# ExtensionConnector.net
KiCad netlist of a schematic drawn in Altium Designer
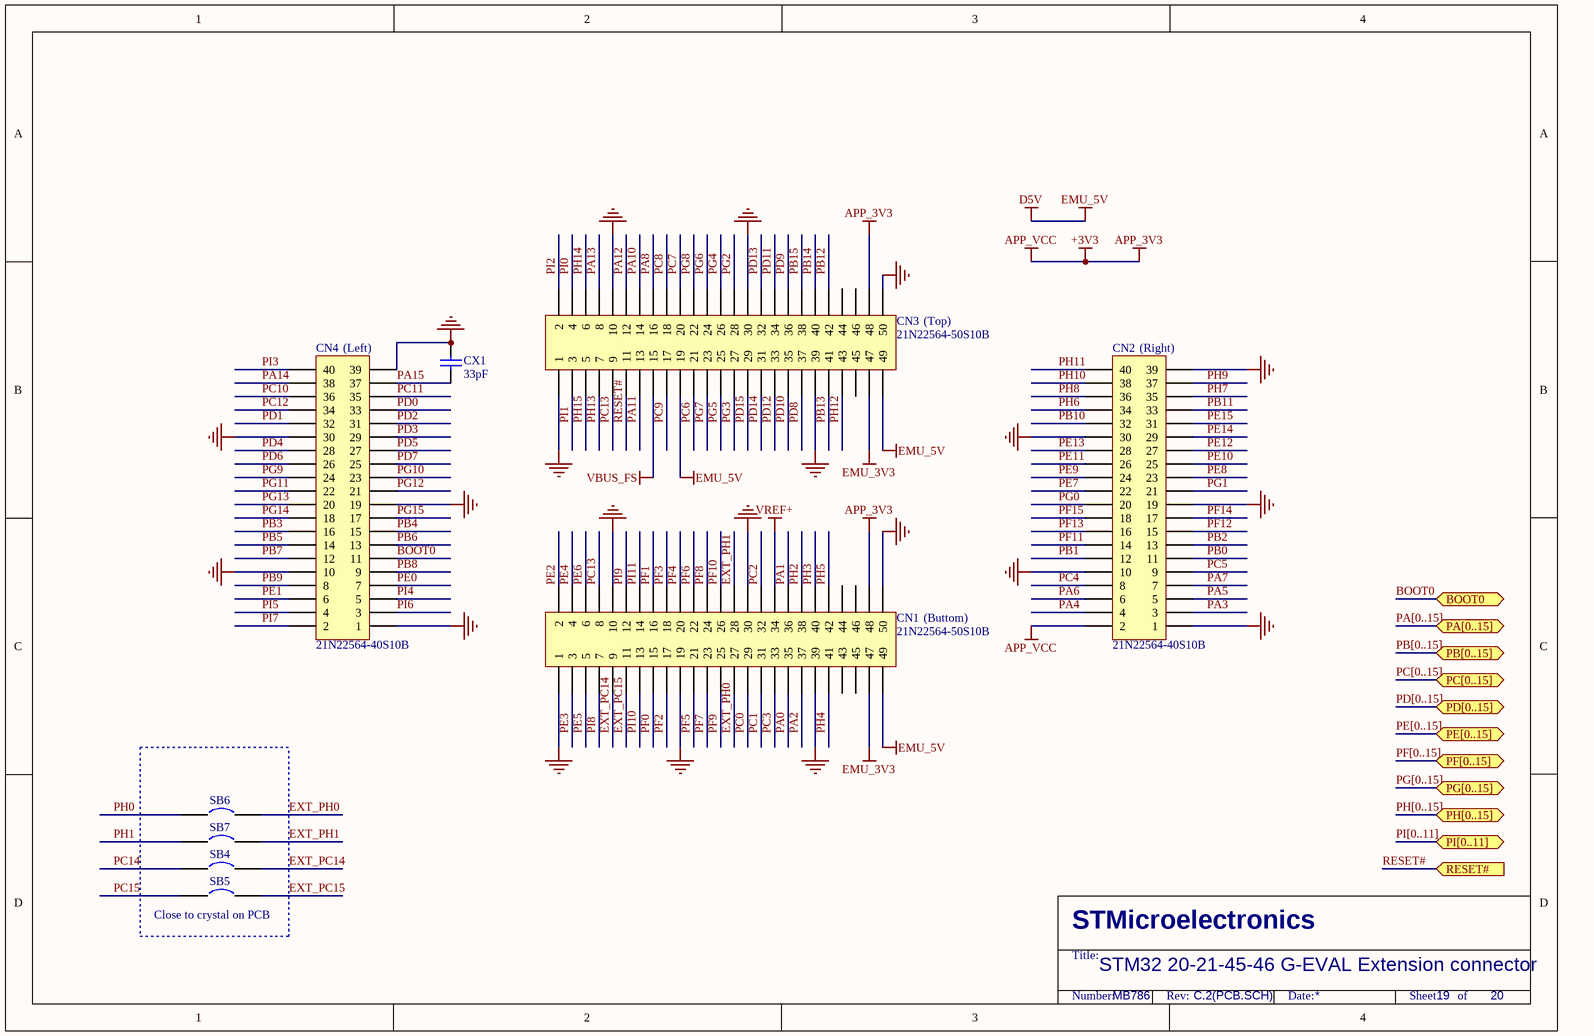
[diagram p0: ExtensionConnector.SchDoc]

(export (version "E")
  (design (tool "Eeschema 10.0.6"))
  (components
    (comp (ref "CN1")
      (value "21N22564-50S10B")
      (footprint "2*25p")
      (description "Header, 25-Pin, Dual row")
      (fields (field (name "PUBLISHER") "Altium Limited"))
      (libsource (lib "Miscellaneous Connectors") (part "Header 25X2"))
    )
    (comp (ref "CN2")
      (value "21N22564-40S10B")
      (footprint "2*20p")
      (description "Header, 20-Pin, Dual row")
      (fields (field (name "PUBLISHER") "Altium Limited"))
      (libsource (lib "Miscellaneous Connectors") (part "Header 20X2"))
    )
    (comp (ref "CN3")
      (value "21N22564-50S10B")
      (footprint "2*25p")
      (description "Header, 25-Pin, Dual row")
      (fields (field (name "PUBLISHER") "Altium Limited"))
      (libsource (lib "Miscellaneous Connectors") (part "Header 25X2"))
    )
    (comp (ref "CN4")
      (value "21N22564-40S10B")
      (footprint "2*20p")
      (description "Header, 20-Pin, Dual row")
      (fields (field (name "PUBLISHER") "Altium Limited"))
      (libsource (lib "Miscellaneous Connectors") (part "Header 20X2"))
    )
    (comp (ref "CX1")
      (value "33pF")
      (footprint "0402C")
      (description "Capacitor")
      (fields (field (name "PUBLISHER") "Altium Limited"))
      (libsource (lib "Miscellaneous Devices") (part "Cap"))
    )
    (comp (ref "SB4")
      (value "~")
      (footprint "JP2_SMD")
      (description "Circuit Breaker")
      (fields (field (name "PUBLISHER") "Altium Limited"))
      (libsource (lib "Miscellaneous Devices") (part "Circuit Breaker"))
    )
    (comp (ref "SB5")
      (value "~")
      (footprint "JP2_SMD")
      (description "Circuit Breaker")
      (fields (field (name "PUBLISHER") "Altium Limited"))
      (libsource (lib "Miscellaneous Devices") (part "Circuit Breaker"))
    )
    (comp (ref "SB6")
      (value "~")
      (footprint "JP2_SMD")
      (description "Circuit Breaker")
      (fields (field (name "PUBLISHER") "Altium Limited"))
      (libsource (lib "Miscellaneous Devices") (part "Circuit Breaker"))
    )
    (comp (ref "SB7")
      (value "~")
      (footprint "JP2_SMD")
      (description "Circuit Breaker")
      (fields (field (name "PUBLISHER") "Altium Limited"))
      (libsource (lib "Miscellaneous Devices") (part "Circuit Breaker"))
    )
  )
  (nets
    (net (code "2") (name "+3V3") (class "Default")
      (node (ref "CN1") (pin "48") (pinfunction "48_48") (pintype "passive"))
      (node (ref "CN2") (pin "2") (pinfunction "2_2") (pintype "passive"))
      (node (ref "CN3") (pin "48") (pinfunction "48_48") (pintype "passive"))
    )
    (net (code "3") (name "/BOOT0") (class "Default")
      (node (ref "CN4") (pin "11") (pinfunction "11_11") (pintype "passive"))
    )
    (net (code "4") (name "/EXT_PC14") (class "Default")
      (node (ref "CN1") (pin "9") (pinfunction "9_9") (pintype "passive"))
      (node (ref "SB4") (pin "2") (pinfunction "2_2") (pintype "passive"))
    )
    (net (code "5") (name "/EXT_PC15") (class "Default")
      (node (ref "CN1") (pin "11") (pinfunction "11_11") (pintype "passive"))
      (node (ref "SB5") (pin "2") (pinfunction "2_2") (pintype "passive"))
    )
    (net (code "6") (name "/EXT_PH0") (class "Default")
      (node (ref "CN1") (pin "27") (pinfunction "27_27") (pintype "passive"))
      (node (ref "SB6") (pin "2") (pinfunction "2_2") (pintype "passive"))
    )
    (net (code "7") (name "/EXT_PH1") (class "Default")
      (node (ref "CN1") (pin "28") (pinfunction "28_28") (pintype "passive"))
      (node (ref "SB7") (pin "2") (pinfunction "2_2") (pintype "passive"))
    )
    (net (code "8") (name "/PA0") (class "Default")
      (node (ref "CN1") (pin "35") (pinfunction "35_35") (pintype "passive"))
    )
    (net (code "9") (name "/PA1") (class "Default")
      (node (ref "CN1") (pin "36") (pinfunction "36_36") (pintype "passive"))
    )
    (net (code "10") (name "/PA2") (class "Default")
      (node (ref "CN1") (pin "37") (pinfunction "37_37") (pintype "passive"))
    )
    (net (code "11") (name "/PA3") (class "Default")
      (node (ref "CN2") (pin "3") (pinfunction "3_3") (pintype "passive"))
    )
    (net (code "12") (name "/PA4") (class "Default")
      (node (ref "CN2") (pin "4") (pinfunction "4_4") (pintype "passive"))
    )
    (net (code "13") (name "/PA5") (class "Default")
      (node (ref "CN2") (pin "5") (pinfunction "5_5") (pintype "passive"))
    )
    (net (code "14") (name "/PA6") (class "Default")
      (node (ref "CN2") (pin "6") (pinfunction "6_6") (pintype "passive"))
    )
    (net (code "15") (name "/PA7") (class "Default")
      (node (ref "CN2") (pin "7") (pinfunction "7_7") (pintype "passive"))
    )
    (net (code "16") (name "/PA8") (class "Default")
      (node (ref "CN3") (pin "16") (pinfunction "16_16") (pintype "passive"))
    )
    (net (code "17") (name "/PA10") (class "Default")
      (node (ref "CN3") (pin "14") (pinfunction "14_14") (pintype "passive"))
    )
    (net (code "18") (name "/PA11") (class "Default")
      (node (ref "CN3") (pin "13") (pinfunction "13_13") (pintype "passive"))
    )
    (net (code "19") (name "/PA12") (class "Default")
      (node (ref "CN3") (pin "12") (pinfunction "12_12") (pintype "passive"))
    )
    (net (code "20") (name "/PA13") (class "Default")
      (node (ref "CN3") (pin "8") (pinfunction "8_8") (pintype "passive"))
    )
    (net (code "21") (name "/PA14") (class "Default")
      (node (ref "CN4") (pin "38") (pinfunction "38_38") (pintype "passive"))
    )
    (net (code "22") (name "/PA15") (class "Default")
      (node (ref "CN4") (pin "37") (pinfunction "37_37") (pintype "passive"))
      (node (ref "CX1") (pin "1") (pinfunction "1_1") (pintype "passive"))
    )
    (net (code "24") (name "/PB0") (class "Default")
      (node (ref "CN2") (pin "11") (pinfunction "11_11") (pintype "passive"))
    )
    (net (code "25") (name "/PB1") (class "Default")
      (node (ref "CN2") (pin "12") (pinfunction "12_12") (pintype "passive"))
    )
    (net (code "26") (name "/PB2") (class "Default")
      (node (ref "CN2") (pin "13") (pinfunction "13_13") (pintype "passive"))
    )
    (net (code "27") (name "/PB3") (class "Default")
      (node (ref "CN4") (pin "16") (pinfunction "16_16") (pintype "passive"))
    )
    (net (code "28") (name "/PB4") (class "Default")
      (node (ref "CN4") (pin "15") (pinfunction "15_15") (pintype "passive"))
    )
    (net (code "29") (name "/PB5") (class "Default")
      (node (ref "CN4") (pin "14") (pinfunction "14_14") (pintype "passive"))
    )
    (net (code "30") (name "/PB6") (class "Default")
      (node (ref "CN4") (pin "13") (pinfunction "13_13") (pintype "passive"))
    )
    (net (code "31") (name "/PB7") (class "Default")
      (node (ref "CN4") (pin "12") (pinfunction "12_12") (pintype "passive"))
    )
    (net (code "32") (name "/PB8") (class "Default")
      (node (ref "CN4") (pin "9") (pinfunction "9_9") (pintype "passive"))
    )
    (net (code "33") (name "/PB9") (class "Default")
      (node (ref "CN4") (pin "8") (pinfunction "8_8") (pintype "passive"))
    )
    (net (code "34") (name "/PB10") (class "Default")
      (node (ref "CN2") (pin "32") (pinfunction "32_32") (pintype "passive"))
    )
    (net (code "35") (name "/PB11") (class "Default")
      (node (ref "CN2") (pin "33") (pinfunction "33_33") (pintype "passive"))
    )
    (net (code "36") (name "/PB12") (class "Default")
      (node (ref "CN3") (pin "42") (pinfunction "42_42") (pintype "passive"))
    )
    (net (code "37") (name "/PB13") (class "Default")
      (node (ref "CN3") (pin "41") (pinfunction "41_41") (pintype "passive"))
    )
    (net (code "38") (name "/PB14") (class "Default")
      (node (ref "CN3") (pin "40") (pinfunction "40_40") (pintype "passive"))
    )
    (net (code "39") (name "/PB15") (class "Default")
      (node (ref "CN3") (pin "38") (pinfunction "38_38") (pintype "passive"))
    )
    (net (code "41") (name "/PC0") (class "Default")
      (node (ref "CN1") (pin "29") (pinfunction "29_29") (pintype "passive"))
    )
    (net (code "42") (name "/PC1") (class "Default")
      (node (ref "CN1") (pin "31") (pinfunction "31_31") (pintype "passive"))
    )
    (net (code "43") (name "/PC2") (class "Default")
      (node (ref "CN1") (pin "32") (pinfunction "32_32") (pintype "passive"))
    )
    (net (code "44") (name "/PC3") (class "Default")
      (node (ref "CN1") (pin "33") (pinfunction "33_33") (pintype "passive"))
    )
    (net (code "45") (name "/PC4") (class "Default")
      (node (ref "CN2") (pin "8") (pinfunction "8_8") (pintype "passive"))
    )
    (net (code "46") (name "/PC5") (class "Default")
      (node (ref "CN2") (pin "9") (pinfunction "9_9") (pintype "passive"))
    )
    (net (code "47") (name "/PC6") (class "Default")
      (node (ref "CN3") (pin "21") (pinfunction "21_21") (pintype "passive"))
    )
    (net (code "48") (name "/PC7") (class "Default")
      (node (ref "CN3") (pin "20") (pinfunction "20_20") (pintype "passive"))
    )
    (net (code "49") (name "/PC8") (class "Default")
      (node (ref "CN3") (pin "18") (pinfunction "18_18") (pintype "passive"))
    )
    (net (code "50") (name "/PC9") (class "Default")
      (node (ref "CN3") (pin "17") (pinfunction "17_17") (pintype "passive"))
    )
    (net (code "51") (name "/PC10") (class "Default")
      (node (ref "CN4") (pin "36") (pinfunction "36_36") (pintype "passive"))
    )
    (net (code "52") (name "/PC11") (class "Default")
      (node (ref "CN4") (pin "35") (pinfunction "35_35") (pintype "passive"))
    )
    (net (code "53") (name "/PC12") (class "Default")
      (node (ref "CN4") (pin "34") (pinfunction "34_34") (pintype "passive"))
    )
    (net (code "54") (name "/PC13") (class "Default")
      (node (ref "CN1") (pin "8") (pinfunction "8_8") (pintype "passive"))
      (node (ref "CN3") (pin "9") (pinfunction "9_9") (pintype "passive"))
    )
    (net (code "55") (name "/PC14") (class "Default")
      (node (ref "SB4") (pin "1") (pinfunction "1_1") (pintype "passive"))
    )
    (net (code "56") (name "/PC15") (class "Default")
      (node (ref "SB5") (pin "1") (pinfunction "1_1") (pintype "passive"))
    )
    (net (code "58") (name "/PD0") (class "Default")
      (node (ref "CN4") (pin "33") (pinfunction "33_33") (pintype "passive"))
    )
    (net (code "59") (name "/PD1") (class "Default")
      (node (ref "CN4") (pin "32") (pinfunction "32_32") (pintype "passive"))
    )
    (net (code "60") (name "/PD2") (class "Default")
      (node (ref "CN4") (pin "31") (pinfunction "31_31") (pintype "passive"))
    )
    (net (code "61") (name "/PD3") (class "Default")
      (node (ref "CN4") (pin "29") (pinfunction "29_29") (pintype "passive"))
    )
    (net (code "62") (name "/PD4") (class "Default")
      (node (ref "CN4") (pin "28") (pinfunction "28_28") (pintype "passive"))
    )
    (net (code "63") (name "/PD5") (class "Default")
      (node (ref "CN4") (pin "27") (pinfunction "27_27") (pintype "passive"))
    )
    (net (code "64") (name "/PD6") (class "Default")
      (node (ref "CN4") (pin "26") (pinfunction "26_26") (pintype "passive"))
    )
    (net (code "65") (name "/PD7") (class "Default")
      (node (ref "CN4") (pin "25") (pinfunction "25_25") (pintype "passive"))
    )
    (net (code "66") (name "/PD8") (class "Default")
      (node (ref "CN3") (pin "37") (pinfunction "37_37") (pintype "passive"))
    )
    (net (code "67") (name "/PD9") (class "Default")
      (node (ref "CN3") (pin "36") (pinfunction "36_36") (pintype "passive"))
    )
    (net (code "68") (name "/PD10") (class "Default")
      (node (ref "CN3") (pin "35") (pinfunction "35_35") (pintype "passive"))
    )
    (net (code "69") (name "/PD11") (class "Default")
      (node (ref "CN3") (pin "34") (pinfunction "34_34") (pintype "passive"))
    )
    (net (code "70") (name "/PD12") (class "Default")
      (node (ref "CN3") (pin "33") (pinfunction "33_33") (pintype "passive"))
    )
    (net (code "71") (name "/PD13") (class "Default")
      (node (ref "CN3") (pin "32") (pinfunction "32_32") (pintype "passive"))
    )
    (net (code "72") (name "/PD14") (class "Default")
      (node (ref "CN3") (pin "31") (pinfunction "31_31") (pintype "passive"))
    )
    (net (code "73") (name "/PD15") (class "Default")
      (node (ref "CN3") (pin "29") (pinfunction "29_29") (pintype "passive"))
    )
    (net (code "75") (name "/PE0") (class "Default")
      (node (ref "CN4") (pin "7") (pinfunction "7_7") (pintype "passive"))
    )
    (net (code "76") (name "/PE1") (class "Default")
      (node (ref "CN4") (pin "6") (pinfunction "6_6") (pintype "passive"))
    )
    (net (code "77") (name "/PE2") (class "Default")
      (node (ref "CN1") (pin "2") (pinfunction "2_2") (pintype "passive"))
    )
    (net (code "78") (name "/PE3") (class "Default")
      (node (ref "CN1") (pin "3") (pinfunction "3_3") (pintype "passive"))
    )
    (net (code "79") (name "/PE4") (class "Default")
      (node (ref "CN1") (pin "4") (pinfunction "4_4") (pintype "passive"))
    )
    (net (code "80") (name "/PE5") (class "Default")
      (node (ref "CN1") (pin "5") (pinfunction "5_5") (pintype "passive"))
    )
    (net (code "81") (name "/PE6") (class "Default")
      (node (ref "CN1") (pin "6") (pinfunction "6_6") (pintype "passive"))
    )
    (net (code "82") (name "/PE7") (class "Default")
      (node (ref "CN2") (pin "22") (pinfunction "22_22") (pintype "passive"))
    )
    (net (code "83") (name "/PE8") (class "Default")
      (node (ref "CN2") (pin "23") (pinfunction "23_23") (pintype "passive"))
    )
    (net (code "84") (name "/PE9") (class "Default")
      (node (ref "CN2") (pin "24") (pinfunction "24_24") (pintype "passive"))
    )
    (net (code "85") (name "/PE10") (class "Default")
      (node (ref "CN2") (pin "25") (pinfunction "25_25") (pintype "passive"))
    )
    (net (code "86") (name "/PE11") (class "Default")
      (node (ref "CN2") (pin "26") (pinfunction "26_26") (pintype "passive"))
    )
    (net (code "87") (name "/PE12") (class "Default")
      (node (ref "CN2") (pin "27") (pinfunction "27_27") (pintype "passive"))
    )
    (net (code "88") (name "/PE13") (class "Default")
      (node (ref "CN2") (pin "28") (pinfunction "28_28") (pintype "passive"))
    )
    (net (code "89") (name "/PE14") (class "Default")
      (node (ref "CN2") (pin "29") (pinfunction "29_29") (pintype "passive"))
    )
    (net (code "90") (name "/PE15") (class "Default")
      (node (ref "CN2") (pin "31") (pinfunction "31_31") (pintype "passive"))
    )
    (net (code "92") (name "/PF0") (class "Default")
      (node (ref "CN1") (pin "15") (pinfunction "15_15") (pintype "passive"))
    )
    (net (code "93") (name "/PF1") (class "Default")
      (node (ref "CN1") (pin "16") (pinfunction "16_16") (pintype "passive"))
    )
    (net (code "94") (name "/PF2") (class "Default")
      (node (ref "CN1") (pin "17") (pinfunction "17_17") (pintype "passive"))
    )
    (net (code "95") (name "/PF3") (class "Default")
      (node (ref "CN1") (pin "18") (pinfunction "18_18") (pintype "passive"))
    )
    (net (code "96") (name "/PF4") (class "Default")
      (node (ref "CN1") (pin "20") (pinfunction "20_20") (pintype "passive"))
    )
    (net (code "97") (name "/PF5") (class "Default")
      (node (ref "CN1") (pin "21") (pinfunction "21_21") (pintype "passive"))
    )
    (net (code "98") (name "/PF6") (class "Default")
      (node (ref "CN1") (pin "22") (pinfunction "22_22") (pintype "passive"))
    )
    (net (code "99") (name "/PF7") (class "Default")
      (node (ref "CN1") (pin "23") (pinfunction "23_23") (pintype "passive"))
    )
    (net (code "100") (name "/PF8") (class "Default")
      (node (ref "CN1") (pin "24") (pinfunction "24_24") (pintype "passive"))
    )
    (net (code "101") (name "/PF9") (class "Default")
      (node (ref "CN1") (pin "25") (pinfunction "25_25") (pintype "passive"))
    )
    (net (code "102") (name "/PF10") (class "Default")
      (node (ref "CN1") (pin "26") (pinfunction "26_26") (pintype "passive"))
    )
    (net (code "103") (name "/PF11") (class "Default")
      (node (ref "CN2") (pin "14") (pinfunction "14_14") (pintype "passive"))
    )
    (net (code "104") (name "/PF12") (class "Default")
      (node (ref "CN2") (pin "15") (pinfunction "15_15") (pintype "passive"))
    )
    (net (code "105") (name "/PF13") (class "Default")
      (node (ref "CN2") (pin "16") (pinfunction "16_16") (pintype "passive"))
    )
    (net (code "106") (name "/PF14") (class "Default")
      (node (ref "CN2") (pin "17") (pinfunction "17_17") (pintype "passive"))
    )
    (net (code "107") (name "/PF15") (class "Default")
      (node (ref "CN2") (pin "18") (pinfunction "18_18") (pintype "passive"))
    )
    (net (code "109") (name "/PG0") (class "Default")
      (node (ref "CN2") (pin "20") (pinfunction "20_20") (pintype "passive"))
    )
    (net (code "110") (name "/PG1") (class "Default")
      (node (ref "CN2") (pin "21") (pinfunction "21_21") (pintype "passive"))
    )
    (net (code "111") (name "/PG2") (class "Default")
      (node (ref "CN3") (pin "28") (pinfunction "28_28") (pintype "passive"))
    )
    (net (code "112") (name "/PG3") (class "Default")
      (node (ref "CN3") (pin "27") (pinfunction "27_27") (pintype "passive"))
    )
    (net (code "113") (name "/PG4") (class "Default")
      (node (ref "CN3") (pin "26") (pinfunction "26_26") (pintype "passive"))
    )
    (net (code "114") (name "/PG5") (class "Default")
      (node (ref "CN3") (pin "25") (pinfunction "25_25") (pintype "passive"))
    )
    (net (code "115") (name "/PG6") (class "Default")
      (node (ref "CN3") (pin "24") (pinfunction "24_24") (pintype "passive"))
    )
    (net (code "116") (name "/PG7") (class "Default")
      (node (ref "CN3") (pin "23") (pinfunction "23_23") (pintype "passive"))
    )
    (net (code "117") (name "/PG8") (class "Default")
      (node (ref "CN3") (pin "22") (pinfunction "22_22") (pintype "passive"))
    )
    (net (code "118") (name "/PG9") (class "Default")
      (node (ref "CN4") (pin "24") (pinfunction "24_24") (pintype "passive"))
    )
    (net (code "119") (name "/PG10") (class "Default")
      (node (ref "CN4") (pin "23") (pinfunction "23_23") (pintype "passive"))
    )
    (net (code "120") (name "/PG11") (class "Default")
      (node (ref "CN4") (pin "22") (pinfunction "22_22") (pintype "passive"))
    )
    (net (code "121") (name "/PG12") (class "Default")
      (node (ref "CN4") (pin "21") (pinfunction "21_21") (pintype "passive"))
    )
    (net (code "122") (name "/PG13") (class "Default")
      (node (ref "CN4") (pin "20") (pinfunction "20_20") (pintype "passive"))
    )
    (net (code "123") (name "/PG14") (class "Default")
      (node (ref "CN4") (pin "18") (pinfunction "18_18") (pintype "passive"))
    )
    (net (code "124") (name "/PG15") (class "Default")
      (node (ref "CN4") (pin "17") (pinfunction "17_17") (pintype "passive"))
    )
    (net (code "126") (name "/PH0") (class "Default")
      (node (ref "SB6") (pin "1") (pinfunction "1_1") (pintype "passive"))
    )
    (net (code "127") (name "/PH1") (class "Default")
      (node (ref "SB7") (pin "1") (pinfunction "1_1") (pintype "passive"))
    )
    (net (code "128") (name "/PH2") (class "Default")
      (node (ref "CN1") (pin "38") (pinfunction "38_38") (pintype "passive"))
    )
    (net (code "129") (name "/PH3") (class "Default")
      (node (ref "CN1") (pin "40") (pinfunction "40_40") (pintype "passive"))
    )
    (net (code "130") (name "/PH4") (class "Default")
      (node (ref "CN1") (pin "41") (pinfunction "41_41") (pintype "passive"))
    )
    (net (code "131") (name "/PH5") (class "Default")
      (node (ref "CN1") (pin "42") (pinfunction "42_42") (pintype "passive"))
    )
    (net (code "132") (name "/PH6") (class "Default")
      (node (ref "CN2") (pin "34") (pinfunction "34_34") (pintype "passive"))
    )
    (net (code "133") (name "/PH7") (class "Default")
      (node (ref "CN2") (pin "35") (pinfunction "35_35") (pintype "passive"))
    )
    (net (code "134") (name "/PH8") (class "Default")
      (node (ref "CN2") (pin "36") (pinfunction "36_36") (pintype "passive"))
    )
    (net (code "135") (name "/PH9") (class "Default")
      (node (ref "CN2") (pin "37") (pinfunction "37_37") (pintype "passive"))
    )
    (net (code "136") (name "/PH10") (class "Default")
      (node (ref "CN2") (pin "38") (pinfunction "38_38") (pintype "passive"))
    )
    (net (code "137") (name "/PH11") (class "Default")
      (node (ref "CN2") (pin "40") (pinfunction "40_40") (pintype "passive"))
    )
    (net (code "138") (name "/PH12") (class "Default")
      (node (ref "CN3") (pin "43") (pinfunction "43_43") (pintype "passive"))
    )
    (net (code "139") (name "/PH13") (class "Default")
      (node (ref "CN3") (pin "7") (pinfunction "7_7") (pintype "passive"))
    )
    (net (code "140") (name "/PH14") (class "Default")
      (node (ref "CN3") (pin "6") (pinfunction "6_6") (pintype "passive"))
    )
    (net (code "141") (name "/PH15") (class "Default")
      (node (ref "CN3") (pin "5") (pinfunction "5_5") (pintype "passive"))
    )
    (net (code "143") (name "/PI0") (class "Default")
      (node (ref "CN3") (pin "4") (pinfunction "4_4") (pintype "passive"))
    )
    (net (code "144") (name "/PI1") (class "Default")
      (node (ref "CN3") (pin "3") (pinfunction "3_3") (pintype "passive"))
    )
    (net (code "145") (name "/PI2") (class "Default")
      (node (ref "CN3") (pin "2") (pinfunction "2_2") (pintype "passive"))
    )
    (net (code "146") (name "/PI3") (class "Default")
      (node (ref "CN4") (pin "40") (pinfunction "40_40") (pintype "passive"))
    )
    (net (code "147") (name "/PI4") (class "Default")
      (node (ref "CN4") (pin "5") (pinfunction "5_5") (pintype "passive"))
    )
    (net (code "148") (name "/PI5") (class "Default")
      (node (ref "CN4") (pin "4") (pinfunction "4_4") (pintype "passive"))
    )
    (net (code "149") (name "/PI6") (class "Default")
      (node (ref "CN4") (pin "3") (pinfunction "3_3") (pintype "passive"))
    )
    (net (code "150") (name "/PI7") (class "Default")
      (node (ref "CN4") (pin "2") (pinfunction "2_2") (pintype "passive"))
    )
    (net (code "151") (name "/PI8") (class "Default")
      (node (ref "CN1") (pin "7") (pinfunction "7_7") (pintype "passive"))
    )
    (net (code "152") (name "/PI9") (class "Default")
      (node (ref "CN1") (pin "12") (pinfunction "12_12") (pintype "passive"))
    )
    (net (code "153") (name "/PI10") (class "Default")
      (node (ref "CN1") (pin "13") (pinfunction "13_13") (pintype "passive"))
    )
    (net (code "154") (name "/PI11") (class "Default")
      (node (ref "CN1") (pin "14") (pinfunction "14_14") (pintype "passive"))
    )
    (net (code "156") (name "/RESET#") (class "Default")
      (node (ref "CN3") (pin "11") (pinfunction "11_11") (pintype "passive"))
    )
    (net (code "157") (name "D5V") (class "Default")
      (node (ref "CN1") (pin "49") (pinfunction "49_49") (pintype "passive"))
      (node (ref "CN3") (pin "19") (pinfunction "19_19") (pintype "passive"))
      (node (ref "CN3") (pin "49") (pinfunction "49_49") (pintype "passive"))
    )
    (net (code "158") (name "EMU_3V3") (class "Default")
      (node (ref "CN1") (pin "47") (pinfunction "47_47") (pintype "passive"))
      (node (ref "CN3") (pin "47") (pinfunction "47_47") (pintype "passive"))
    )
    (net (code "159") (name "GND") (class "Default")
      (node (ref "CN1") (pin "1") (pinfunction "1_1") (pintype "passive"))
      (node (ref "CN1") (pin "10") (pinfunction "10_10") (pintype "passive"))
      (node (ref "CN1") (pin "19") (pinfunction "19_19") (pintype "passive"))
      (node (ref "CN1") (pin "30") (pinfunction "30_30") (pintype "passive"))
      (node (ref "CN1") (pin "39") (pinfunction "39_39") (pintype "passive"))
      (node (ref "CN1") (pin "50") (pinfunction "50_50") (pintype "passive"))
      (node (ref "CN2") (pin "1") (pinfunction "1_1") (pintype "passive"))
      (node (ref "CN2") (pin "10") (pinfunction "10_10") (pintype "passive"))
      (node (ref "CN2") (pin "19") (pinfunction "19_19") (pintype "passive"))
      (node (ref "CN2") (pin "30") (pinfunction "30_30") (pintype "passive"))
      (node (ref "CN2") (pin "39") (pinfunction "39_39") (pintype "passive"))
      (node (ref "CN3") (pin "1") (pinfunction "1_1") (pintype "passive"))
      (node (ref "CN3") (pin "10") (pinfunction "10_10") (pintype "passive"))
      (node (ref "CN3") (pin "30") (pinfunction "30_30") (pintype "passive"))
      (node (ref "CN3") (pin "39") (pinfunction "39_39") (pintype "passive"))
      (node (ref "CN3") (pin "50") (pinfunction "50_50") (pintype "passive"))
      (node (ref "CN4") (pin "1") (pinfunction "1_1") (pintype "passive"))
      (node (ref "CN4") (pin "10") (pinfunction "10_10") (pintype "passive"))
      (node (ref "CN4") (pin "19") (pinfunction "19_19") (pintype "passive"))
      (node (ref "CN4") (pin "30") (pinfunction "30_30") (pintype "passive"))
      (node (ref "CN4") (pin "39") (pinfunction "39_39") (pintype "passive"))
      (node (ref "CX1") (pin "2") (pinfunction "2_2") (pintype "passive"))
    )
    (net (code "160") (name "VBUS_FS") (class "Default")
      (node (ref "CN3") (pin "15") (pinfunction "15_15") (pintype "passive"))
    )
    (net (code "161") (name "VREF+") (class "Default")
      (node (ref "CN1") (pin "34") (pinfunction "34_34") (pintype "passive"))
    )
    (net (code "162") (name "unconnected-(CN1-Pad43)") (class "Default")
      (node (ref "CN1") (pin "43") (pinfunction "43_43") (pintype "passive"))
    )
    (net (code "163") (name "unconnected-(CN1-Pad44)") (class "Default")
      (node (ref "CN1") (pin "44") (pinfunction "44_44") (pintype "passive"))
    )
    (net (code "164") (name "unconnected-(CN1-Pad45)") (class "Default")
      (node (ref "CN1") (pin "45") (pinfunction "45_45") (pintype "passive"))
    )
    (net (code "165") (name "unconnected-(CN1-Pad46)") (class "Default")
      (node (ref "CN1") (pin "46") (pinfunction "46_46") (pintype "passive"))
    )
    (net (code "166") (name "unconnected-(CN3-Pad44)") (class "Default")
      (node (ref "CN3") (pin "44") (pinfunction "44_44") (pintype "passive"))
    )
    (net (code "167") (name "unconnected-(CN3-Pad45)") (class "Default")
      (node (ref "CN3") (pin "45") (pinfunction "45_45") (pintype "passive"))
    )
    (net (code "168") (name "unconnected-(CN3-Pad46)") (class "Default")
      (node (ref "CN3") (pin "46") (pinfunction "46_46") (pintype "passive"))
    )
  )
)
